# CPU.net
KiCad netlist of a schematic drawn in Altium Designer
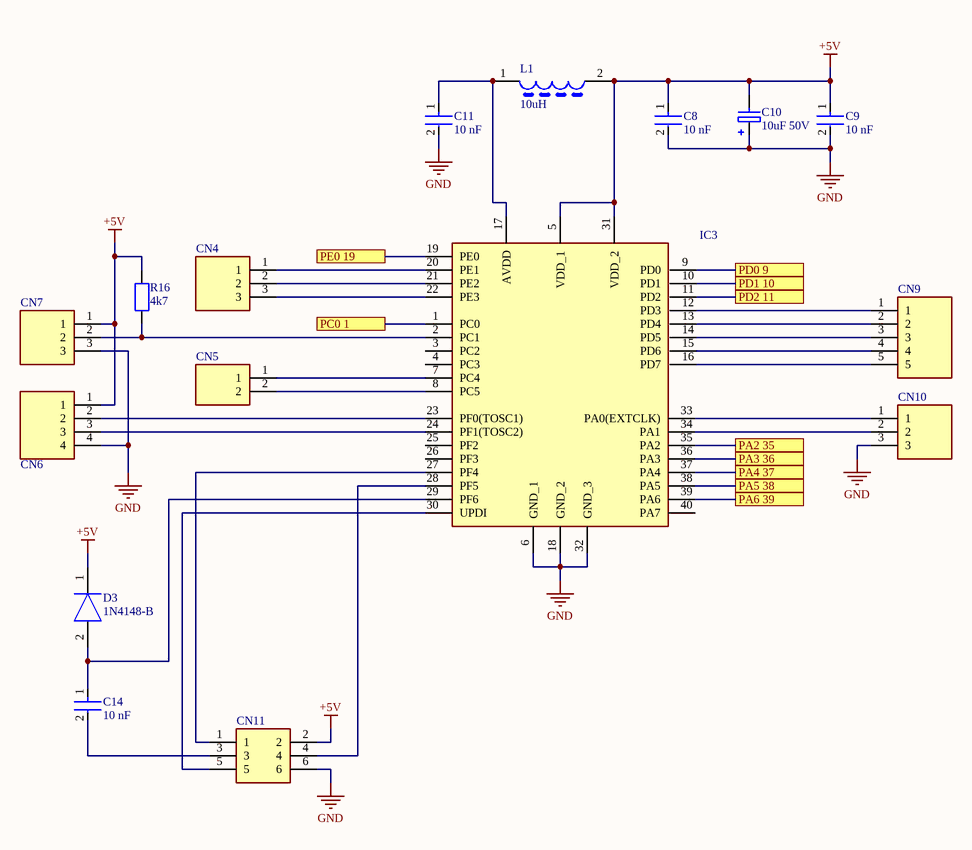
[diagram p0: CPU.SchDoc]

(export (version "E")
  (design (tool "Eeschema 10.0.6"))
  (components
    (comp (ref "C8")
      (value "10 nF")
      (footprint "0805")
      (description "Chip Multilayer Ceramic Capacitors for General Purpose, 0805, 10uF, X5R, 15%, 10%, 25V")
      (fields (field (name "VOLTAGE") "25V") (field (name "TOLERANCE") "10%"))
      (libsource (lib "Schlib1") (part "Condensator 0805"))
    )
    (comp (ref "C9")
      (value "10 nF")
      (footprint "0805")
      (description "Chip Multilayer Ceramic Capacitors for General Purpose, 0805, 10uF, X5R, 15%, 10%, 25V")
      (fields (field (name "VOLTAGE") "25V") (field (name "TOLERANCE") "10%"))
      (libsource (lib "Schlib1") (part "Condensator 0805"))
    )
    (comp (ref "C10")
      (value "10uF 50V")
      (footprint "Elco 100uF 25V")
      (fields
        (field (name "PART NUMBER") "02015A270JAT2A")
        (field (name "MANUFACTURER") "AVX Interconnect / Elco")
      )
      (libsource (lib "Schlib1") (part "Condensator Elco"))
    )
    (comp (ref "C11")
      (value "10 nF")
      (footprint "0805")
      (description "Chip Multilayer Ceramic Capacitors for General Purpose, 0805, 10uF, X5R, 15%, 10%, 25V")
      (fields (field (name "VOLTAGE") "25V") (field (name "TOLERANCE") "10%"))
      (libsource (lib "Schlib1") (part "Condensator 0805"))
    )
    (comp (ref "C14")
      (value "10 nF")
      (footprint "0805")
      (description "Chip Multilayer Ceramic Capacitors for General Purpose, 0805, 10uF, X5R, 15%, 10%, 25V")
      (fields (field (name "VOLTAGE") "25V") (field (name "TOLERANCE") "10%"))
      (libsource (lib "Schlib1") (part "Condensator 0805"))
    )
    (comp (ref "CN4")
      (value "5-146280-3")
      (footprint "SamacSys:HDRV3W97P0X254_1X3_721X234X821P")
      (description "Connector 5-146280-3")
      (fields (field (name "MOUSER2 PART NUMBER") "571-5-146280-3"))
      (libsource (lib "Schlib1") (part "3 Pin Header L"))
    )
    (comp (ref "CN5")
      (value "5-146280-2")
      (footprint "SamacSys:HDRV2W77P0X254_1X2_467X234X872P")
      (description "Connector")
      (libsource (lib "Schlib1") (part "2 Pin Header L"))
    )
    (comp (ref "CN6")
      (value "5-146280-4")
      (footprint "SamacSys:HDRV4W77P254_4X1_467X488X821P")
      (description "Connector 5-146280-4")
      (libsource (lib "Schlib1") (part "4 Pin Header L"))
    )
    (comp (ref "CN7")
      (value "5-146280-3")
      (footprint "SamacSys:HDRV3W97P0X254_1X3_721X234X821P")
      (description "Connector 5-146280-3")
      (fields (field (name "MOUSER2 PART NUMBER") "571-5-146280-3"))
      (libsource (lib "Schlib1") (part "3 Pin Header L"))
    )
    (comp (ref "CN9")
      (value "5-146280-5")
      (footprint "SamacSys:HDRV5W67P0X254_1X5_1229X234X821P")
      (description "Connector 5-146280-5")
      (fields (field (name "MOUSER2 PART NUMBER") "571-5-146280-5"))
      (libsource (lib "Schlib1") (part "5 Pin Header"))
    )
    (comp (ref "CN10")
      (value "5-146280-3")
      (footprint "SamacSys:HDRV3W97P0X254_1X3_721X234X821P")
      (description "Connector 5-146280-3")
      (fields (field (name "MOUSER2 PART NUMBER") "571-5-146280-3"))
      (libsource (lib "Schlib1") (part "3 Pin Header"))
    )
    (comp (ref "CN11")
      (value "2x3 Pin Header")
      (footprint "SamacSys:HDRV6W67P254_2X3_721X488X872P")
      (description "Connector")
      (fields (field (name "MANUFACTURER_PART_NUMBER") "5-146256-3"))
      (libsource (lib "Schlib1") (part "2x3 Pin Header"))
    )
    (comp (ref "D3")
      (value "1N4148-B")
      (footprint "SamacSys:DIOAD1220W56L420D200")
      (description "Diode")
      (libsource (lib "*") (part "1N4148-B"))
    )
    (comp (ref "IC3")
      (value "ATMEGA4809-PF")
      (footprint "SamacSys:DIP1543W58P254L5175H635Q40N")
      (description "Integrated Circuit")
      (fields (field (name "MOUSER2 PART NUMBER") "556-ATMEGA4809-PF"))
      (libsource (lib "Schlib1") (part "ATMEGA4809-PF"))
    )
    (comp (ref "L1")
      (value "10uH")
      (footprint "SamacSys:VLS6045")
      (description "Inductor VLS6045EX-100M-H")
      (fields
        (field (name "MOUSER2 PART NUMBER") "810-VLS6045EX-100M-H")
        (field (name "MANUFACTURER_PART_NUMBER") "VLS6045EX-100M-H")
      )
      (libsource (lib "Schlib1") (part "Smoorspoel"))
    )
    (comp (ref "R16")
      (value "4k7")
      (footprint "0805")
      (fields (field (name "MANUFACTURER") "Vishay Dale") (field (name "PART NUMBER") "CRCW08050000Z0EA"))
      (libsource (lib "Schlib1") (part "Resistor 0805"))
    )
  )
  (nets
    (net (code "1") (name "+5V") (class "Default")
      (node (ref "C10") (pin "2") (pinfunction "2_2") (pintype "passive"))
      (node (ref "C8") (pin "1") (pinfunction "1_1") (pintype "passive"))
      (node (ref "C9") (pin "1") (pinfunction "1_1") (pintype "passive"))
      (node (ref "CN11") (pin "2") (pinfunction "2_2") (pintype "passive"))
      (node (ref "CN6") (pin "1") (pinfunction "1_1") (pintype "passive"))
      (node (ref "CN7") (pin "1") (pinfunction "1_1") (pintype "passive"))
      (node (ref "D3") (pin "1") (pinfunction "K_1") (pintype "passive"))
      (node (ref "IC3") (pin "31") (pinfunction "VDD_2_31") (pintype "passive"))
      (node (ref "IC3") (pin "5") (pinfunction "VDD_1_5") (pintype "passive"))
      (node (ref "L1") (pin "2") (pinfunction "2_2") (pintype "passive"))
      (node (ref "R16") (pin "1") (pinfunction "1_1") (pintype "passive"))
    )
    (net (code "2") (name "/PA2 35") (class "Default")
      (node (ref "IC3") (pin "35") (pinfunction "PA2_35") (pintype "passive"))
    )
    (net (code "3") (name "/PA3 36") (class "Default")
      (node (ref "IC3") (pin "36") (pinfunction "PA3_36") (pintype "passive"))
    )
    (net (code "4") (name "/PA4 37") (class "Default")
      (node (ref "IC3") (pin "37") (pinfunction "PA4_37") (pintype "passive"))
    )
    (net (code "5") (name "/PA5 38") (class "Default")
      (node (ref "IC3") (pin "38") (pinfunction "PA5_38") (pintype "passive"))
    )
    (net (code "6") (name "/PA6 39") (class "Default")
      (node (ref "IC3") (pin "39") (pinfunction "PA6_39") (pintype "passive"))
    )
    (net (code "7") (name "/PC0 1") (class "Default")
      (node (ref "IC3") (pin "1") (pinfunction "PC0_1") (pintype "passive"))
    )
    (net (code "8") (name "/PD0 9") (class "Default")
      (node (ref "IC3") (pin "9") (pinfunction "PD0_9") (pintype "passive"))
    )
    (net (code "9") (name "/PD1 10") (class "Default")
      (node (ref "IC3") (pin "10") (pinfunction "PD1_10") (pintype "passive"))
    )
    (net (code "10") (name "/PD2 11") (class "Default")
      (node (ref "IC3") (pin "11") (pinfunction "PD2_11") (pintype "passive"))
    )
    (net (code "11") (name "/PE0 19") (class "Default")
      (node (ref "IC3") (pin "19") (pinfunction "PE0_19") (pintype "passive"))
    )
    (net (code "12") (name "GND") (class "Default")
      (node (ref "C10") (pin "1") (pinfunction "1_1") (pintype "passive"))
      (node (ref "C11") (pin "2") (pinfunction "2_2") (pintype "passive"))
      (node (ref "C8") (pin "2") (pinfunction "2_2") (pintype "passive"))
      (node (ref "C9") (pin "2") (pinfunction "2_2") (pintype "passive"))
      (node (ref "CN10") (pin "3") (pinfunction "3_3") (pintype "passive"))
      (node (ref "CN11") (pin "6") (pinfunction "6_6") (pintype "passive"))
      (node (ref "CN6") (pin "4") (pinfunction "4_4") (pintype "passive"))
      (node (ref "CN7") (pin "3") (pinfunction "3_3") (pintype "passive"))
      (node (ref "IC3") (pin "18") (pinfunction "GND_2_18") (pintype "passive"))
      (node (ref "IC3") (pin "32") (pinfunction "GND_3_32") (pintype "passive"))
      (node (ref "IC3") (pin "6") (pinfunction "GND_1_6") (pintype "passive"))
    )
    (net (code "13") (name "Net-(C14-Pad2)") (class "Default")
      (node (ref "C14") (pin "2") (pinfunction "2_2") (pintype "passive"))
      (node (ref "CN11") (pin "3") (pinfunction "3_3") (pintype "passive"))
    )
    (net (code "14") (name "Net-(D3-A)") (class "Default")
      (node (ref "C14") (pin "1") (pinfunction "1_1") (pintype "passive"))
      (node (ref "D3") (pin "2") (pinfunction "A_2") (pintype "passive"))
      (node (ref "IC3") (pin "29") (pinfunction "PF6_29") (pintype "passive"))
    )
    (net (code "15") (name "Net-(IC3-AVDD)") (class "Default")
      (node (ref "C11") (pin "1") (pinfunction "1_1") (pintype "passive"))
      (node (ref "IC3") (pin "17") (pinfunction "AVDD_17") (pintype "passive"))
      (node (ref "L1") (pin "1") (pinfunction "1_1") (pintype "passive"))
    )
    (net (code "16") (name "Net-(IC3-PA0(EXTCLK))") (class "Default")
      (node (ref "CN10") (pin "1") (pinfunction "1_1") (pintype "passive"))
      (node (ref "IC3") (pin "33") (pinfunction "PA0(EXTCLK)_33") (pintype "passive"))
    )
    (net (code "17") (name "Net-(IC3-PA1)") (class "Default")
      (node (ref "CN10") (pin "2") (pinfunction "2_2") (pintype "passive"))
      (node (ref "IC3") (pin "34") (pinfunction "PA1_34") (pintype "passive"))
    )
    (net (code "18") (name "Net-(IC3-PC1)") (class "Default")
      (node (ref "CN7") (pin "2") (pinfunction "2_2") (pintype "passive"))
      (node (ref "IC3") (pin "2") (pinfunction "PC1_2") (pintype "passive"))
      (node (ref "R16") (pin "2") (pinfunction "2_2") (pintype "passive"))
    )
    (net (code "19") (name "Net-(IC3-PC4)") (class "Default")
      (node (ref "CN5") (pin "1") (pinfunction "1_1") (pintype "passive"))
      (node (ref "IC3") (pin "7") (pinfunction "PC4_7") (pintype "passive"))
    )
    (net (code "20") (name "Net-(IC3-PC5)") (class "Default")
      (node (ref "CN5") (pin "2") (pinfunction "2_2") (pintype "passive"))
      (node (ref "IC3") (pin "8") (pinfunction "PC5_8") (pintype "passive"))
    )
    (net (code "21") (name "Net-(IC3-PD3)") (class "Default")
      (node (ref "CN9") (pin "1") (pinfunction "1_1") (pintype "passive"))
      (node (ref "IC3") (pin "12") (pinfunction "PD3_12") (pintype "passive"))
    )
    (net (code "22") (name "Net-(IC3-PD4)") (class "Default")
      (node (ref "CN9") (pin "2") (pinfunction "2_2") (pintype "passive"))
      (node (ref "IC3") (pin "13") (pinfunction "PD4_13") (pintype "passive"))
    )
    (net (code "23") (name "Net-(IC3-PD5)") (class "Default")
      (node (ref "CN9") (pin "3") (pinfunction "3_3") (pintype "passive"))
      (node (ref "IC3") (pin "14") (pinfunction "PD5_14") (pintype "passive"))
    )
    (net (code "24") (name "Net-(IC3-PD6)") (class "Default")
      (node (ref "CN9") (pin "4") (pinfunction "4_4") (pintype "passive"))
      (node (ref "IC3") (pin "15") (pinfunction "PD6_15") (pintype "passive"))
    )
    (net (code "25") (name "Net-(IC3-PD7)") (class "Default")
      (node (ref "CN9") (pin "5") (pinfunction "5_5") (pintype "passive"))
      (node (ref "IC3") (pin "16") (pinfunction "PD7_16") (pintype "passive"))
    )
    (net (code "26") (name "Net-(IC3-PE1)") (class "Default")
      (node (ref "CN4") (pin "1") (pinfunction "1_1") (pintype "passive"))
      (node (ref "IC3") (pin "20") (pinfunction "PE1_20") (pintype "passive"))
    )
    (net (code "27") (name "Net-(IC3-PE2)") (class "Default")
      (node (ref "CN4") (pin "2") (pinfunction "2_2") (pintype "passive"))
      (node (ref "IC3") (pin "21") (pinfunction "PE2_21") (pintype "passive"))
    )
    (net (code "28") (name "Net-(IC3-PE3)") (class "Default")
      (node (ref "CN4") (pin "3") (pinfunction "3_3") (pintype "passive"))
      (node (ref "IC3") (pin "22") (pinfunction "PE3_22") (pintype "passive"))
    )
    (net (code "29") (name "Net-(IC3-PF0(TOSC1))") (class "Default")
      (node (ref "CN6") (pin "2") (pinfunction "2_2") (pintype "passive"))
      (node (ref "IC3") (pin "23") (pinfunction "PF0(TOSC1)_23") (pintype "passive"))
    )
    (net (code "30") (name "Net-(IC3-PF1(TOSC2))") (class "Default")
      (node (ref "CN6") (pin "3") (pinfunction "3_3") (pintype "passive"))
      (node (ref "IC3") (pin "24") (pinfunction "PF1(TOSC2)_24") (pintype "passive"))
    )
    (net (code "31") (name "Net-(IC3-PF4)") (class "Default")
      (node (ref "CN11") (pin "1") (pinfunction "1_1") (pintype "passive"))
      (node (ref "IC3") (pin "27") (pinfunction "PF4_27") (pintype "passive"))
    )
    (net (code "32") (name "Net-(IC3-PF5)") (class "Default")
      (node (ref "CN11") (pin "4") (pinfunction "4_4") (pintype "passive"))
      (node (ref "IC3") (pin "28") (pinfunction "PF5_28") (pintype "passive"))
    )
    (net (code "33") (name "Net-(IC3-UPDI)") (class "Default")
      (node (ref "CN11") (pin "5") (pinfunction "5_5") (pintype "passive"))
      (node (ref "IC3") (pin "30") (pinfunction "UPDI_30") (pintype "passive"))
    )
    (net (code "34") (name "unconnected-(IC3-PA7-Pad40)") (class "Default")
      (node (ref "IC3") (pin "40") (pinfunction "PA7_40") (pintype "passive"))
    )
    (net (code "35") (name "unconnected-(IC3-PC2-Pad3)") (class "Default")
      (node (ref "IC3") (pin "3") (pinfunction "PC2_3") (pintype "passive"))
    )
    (net (code "36") (name "unconnected-(IC3-PC3-Pad4)") (class "Default")
      (node (ref "IC3") (pin "4") (pinfunction "PC3_4") (pintype "passive"))
    )
    (net (code "37") (name "unconnected-(IC3-PF2-Pad25)") (class "Default")
      (node (ref "IC3") (pin "25") (pinfunction "PF2_25") (pintype "passive"))
    )
    (net (code "38") (name "unconnected-(IC3-PF3-Pad26)") (class "Default")
      (node (ref "IC3") (pin "26") (pinfunction "PF3_26") (pintype "passive"))
    )
  )
)
